# chessbot1final.net
KiCad netlist of a schematic drawn in EAGLE
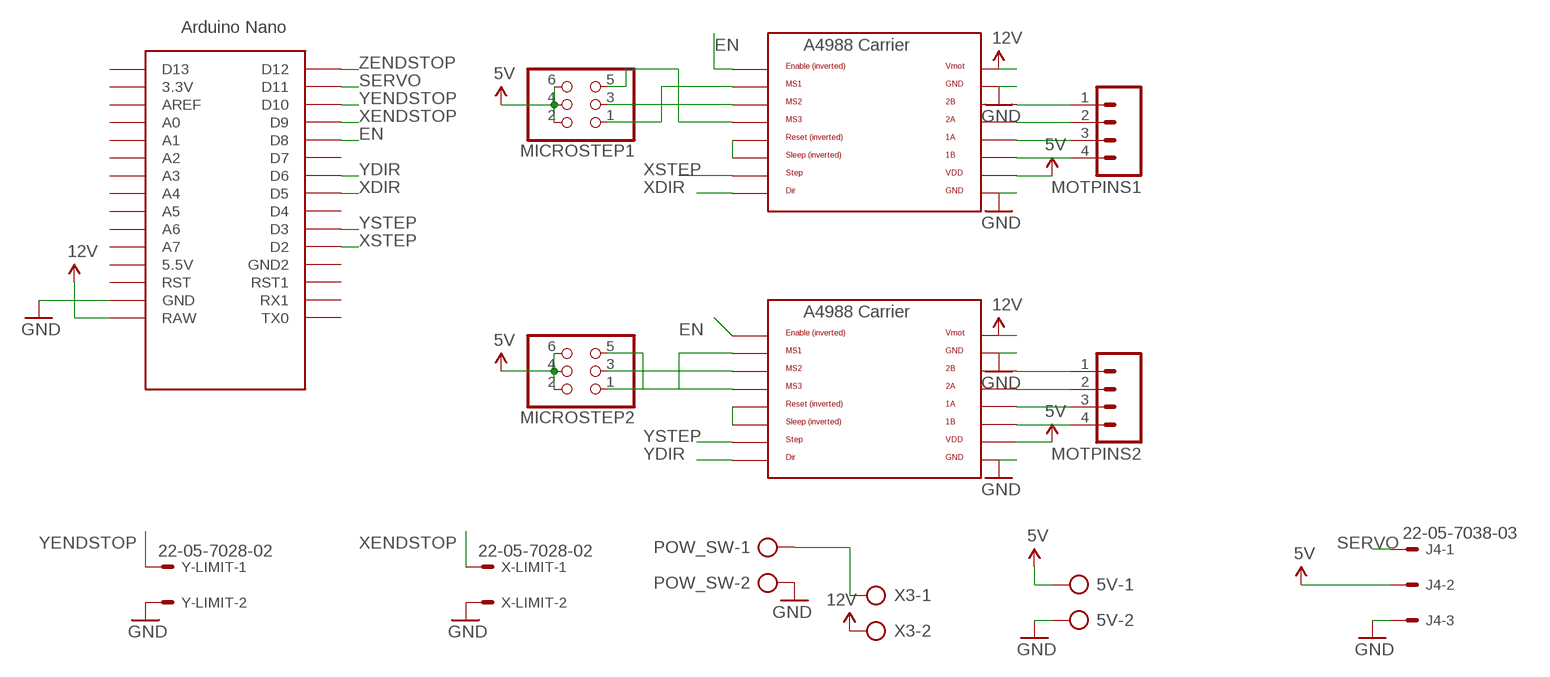
[diagram p0: schematic, sheet 1]

(export (version "E")
  (design (tool "Eeschema 10.0.6"))
  (components
    (comp (ref "5V")
      (value "AK500/2")
      (footprint "eagle-import:AK500_2")
      (libsource (lib "eagle-import") (part "AK500/2"))
    )
    (comp (ref "J4")
      (value "22-05-7038-03")
      (footprint "eagle-import:7395-03")
      (libsource (lib "eagle-import") (part "22-?-0305-7038"))
    )
    (comp (ref "MICROSTEP1")
      (value "PINHD-2X3")
      (footprint "eagle-import:2X03")
      (libsource (lib "eagle-import") (part "PINHD-2X3"))
    )
    (comp (ref "MICROSTEP2")
      (value "PINHD-2X3")
      (footprint "eagle-import:2X03")
      (libsource (lib "eagle-import") (part "PINHD-2X3"))
    )
    (comp (ref "MOTPINS1")
      (value "M04PTH")
      (footprint "eagle-import:1X04")
      (libsource (lib "eagle-import") (part "M04PTH"))
    )
    (comp (ref "MOTPINS2")
      (value "M04PTH")
      (footprint "eagle-import:1X04")
      (libsource (lib "eagle-import") (part "M04PTH"))
    )
    (comp (ref "POW_SW")
      (value "AK500/2")
      (footprint "eagle-import:AK500_2")
      (libsource (lib "eagle-import") (part "AK500/2"))
    )
    (comp (ref "U$1")
      (value "A4988BREAKOUT")
      (footprint "eagle-import:A4988BREAKOUT")
      (libsource (lib "eagle-import") (part "A4988BREAKOUT"))
    )
    (comp (ref "U$2")
      (value "A4988BREAKOUT")
      (footprint "eagle-import:A4988BREAKOUT")
      (libsource (lib "eagle-import") (part "A4988BREAKOUT"))
    )
    (comp (ref "U$3")
      (value "NANO")
      (footprint "eagle-import:NANO")
      (libsource (lib "eagle-import") (part "NANO"))
    )
    (comp (ref "X-LIMIT")
      (value "22-05-7028-02")
      (footprint "eagle-import:7395-02")
      (libsource (lib "eagle-import") (part "22-?-0205-7028"))
    )
    (comp (ref "X3")
      (value "AK500/2")
      (footprint "eagle-import:AK500_2")
      (libsource (lib "eagle-import") (part "AK500/2"))
    )
    (comp (ref "Y-LIMIT")
      (value "22-05-7028-02")
      (footprint "eagle-import:7395-02")
      (libsource (lib "eagle-import") (part "22-?-0205-7028"))
    )
  )
  (nets
    (net (code "1") (name "/EN") (class "Default")
      (node (ref "U$1") (pin "EN") (pinfunction "EN_EN") (pintype "input"))
      (node (ref "U$2") (pin "EN") (pinfunction "EN_EN") (pintype "input"))
      (node (ref "U$3") (pin "D8") (pinfunction "D8_D8") (pintype "bidirectional"))
    )
    (net (code "2") (name "/SERVO") (class "Default")
      (node (ref "J4") (pin "1") (pinfunction "S_1") (pintype "passive"))
      (node (ref "U$3") (pin "D11") (pinfunction "D11_D11") (pintype "bidirectional"))
    )
    (net (code "3") (name "/XDIR") (class "Default")
      (node (ref "U$2") (pin "DIR") (pinfunction "DIR_DIR") (pintype "input"))
      (node (ref "U$3") (pin "D5") (pinfunction "D5_D5") (pintype "bidirectional"))
    )
    (net (code "4") (name "/XENDSTOP") (class "Default")
      (node (ref "U$3") (pin "D9") (pinfunction "D9_D9") (pintype "bidirectional"))
      (node (ref "X-LIMIT") (pin "1") (pinfunction "S_1") (pintype "passive"))
    )
    (net (code "5") (name "/XSTEP") (class "Default")
      (node (ref "U$2") (pin "STEP") (pinfunction "STEP_STEP") (pintype "input"))
      (node (ref "U$3") (pin "D2") (pinfunction "D2_D2") (pintype "bidirectional"))
    )
    (net (code "6") (name "/YDIR") (class "Default")
      (node (ref "U$1") (pin "DIR") (pinfunction "DIR_DIR") (pintype "input"))
      (node (ref "U$3") (pin "D6") (pinfunction "D6_D6") (pintype "bidirectional"))
    )
    (net (code "7") (name "/YENDSTOP") (class "Default")
      (node (ref "U$3") (pin "D10") (pinfunction "D10_D10") (pintype "bidirectional"))
      (node (ref "Y-LIMIT") (pin "1") (pinfunction "S_1") (pintype "passive"))
    )
    (net (code "8") (name "/YSTEP") (class "Default")
      (node (ref "U$1") (pin "STEP") (pinfunction "STEP_STEP") (pintype "input"))
      (node (ref "U$3") (pin "D3") (pinfunction "D3_D3") (pintype "bidirectional"))
    )
    (net (code "9") (name "/ZENDSTOP") (class "Default")
      (node (ref "U$3") (pin "D12") (pinfunction "D12_D12") (pintype "bidirectional"))
    )
    (net (code "10") (name "5V") (class "Default")
      (node (ref "5V") (pin "1") (pinfunction "KL_1") (pintype "passive"))
      (node (ref "J4") (pin "2") (pinfunction "S_2") (pintype "passive"))
      (node (ref "MICROSTEP1") (pin "2") (pinfunction "2_2") (pintype "passive"))
      (node (ref "MICROSTEP1") (pin "4") (pinfunction "4_4") (pintype "passive"))
      (node (ref "MICROSTEP1") (pin "6") (pinfunction "6_6") (pintype "passive"))
      (node (ref "MICROSTEP2") (pin "2") (pinfunction "2_2") (pintype "passive"))
      (node (ref "MICROSTEP2") (pin "4") (pinfunction "4_4") (pintype "passive"))
      (node (ref "MICROSTEP2") (pin "6") (pinfunction "6_6") (pintype "passive"))
      (node (ref "U$1") (pin "VDD") (pinfunction "VDD_VDD") (pintype "power_in"))
      (node (ref "U$2") (pin "VDD") (pinfunction "VDD_VDD") (pintype "power_in"))
    )
    (net (code "11") (name "12V") (class "Default")
      (node (ref "U$1") (pin "VMOT") (pinfunction "VMOT_VMOT") (pintype "power_in"))
      (node (ref "U$2") (pin "VMOT") (pinfunction "VMOT_VMOT") (pintype "power_in"))
      (node (ref "U$3") (pin "RAW") (pinfunction "RAW_RAW") (pintype "bidirectional"))
      (node (ref "X3") (pin "2") (pinfunction "KL_2") (pintype "passive"))
    )
    (net (code "12") (name "GND") (class "Default")
      (node (ref "5V") (pin "2") (pinfunction "KL_2") (pintype "passive"))
      (node (ref "J4") (pin "3") (pinfunction "S_3") (pintype "passive"))
      (node (ref "POW_SW") (pin "2") (pinfunction "KL_2") (pintype "passive"))
      (node (ref "U$1") (pin "GND") (pinfunction "GND_GND") (pintype "power_in"))
      (node (ref "U$1") (pin "GND@0") (pinfunction "GND_GND@0") (pintype "power_in"))
      (node (ref "U$2") (pin "GND") (pinfunction "GND_GND") (pintype "power_in"))
      (node (ref "U$2") (pin "GND@0") (pinfunction "GND_GND@0") (pintype "power_in"))
      (node (ref "U$3") (pin "GND") (pinfunction "GND_GND") (pintype "bidirectional"))
      (node (ref "X-LIMIT") (pin "2") (pinfunction "S_2") (pintype "passive"))
      (node (ref "Y-LIMIT") (pin "2") (pinfunction "S_2") (pintype "passive"))
    )
    (net (code "13") (name "Net-(MICROSTEP1-Pad1)") (class "Default")
      (node (ref "MICROSTEP1") (pin "1") (pinfunction "1_1") (pintype "passive"))
      (node (ref "U$2") (pin "MS1") (pinfunction "MS1_MS1") (pintype "input"))
    )
    (net (code "14") (name "Net-(MICROSTEP1-Pad3)") (class "Default")
      (node (ref "MICROSTEP1") (pin "3") (pinfunction "3_3") (pintype "passive"))
      (node (ref "U$2") (pin "MS2") (pinfunction "MS2_MS2") (pintype "input"))
    )
    (net (code "15") (name "Net-(MICROSTEP1-Pad5)") (class "Default")
      (node (ref "MICROSTEP1") (pin "5") (pinfunction "5_5") (pintype "passive"))
      (node (ref "U$2") (pin "MS3") (pinfunction "MS3_MS3") (pintype "input"))
    )
    (net (code "16") (name "Net-(MICROSTEP2-Pad1)") (class "Default")
      (node (ref "MICROSTEP2") (pin "1") (pinfunction "1_1") (pintype "passive"))
      (node (ref "U$1") (pin "MS1") (pinfunction "MS1_MS1") (pintype "input"))
    )
    (net (code "17") (name "Net-(MICROSTEP2-Pad3)") (class "Default")
      (node (ref "MICROSTEP2") (pin "3") (pinfunction "3_3") (pintype "passive"))
      (node (ref "U$1") (pin "MS2") (pinfunction "MS2_MS2") (pintype "input"))
    )
    (net (code "18") (name "Net-(MICROSTEP2-Pad5)") (class "Default")
      (node (ref "MICROSTEP2") (pin "5") (pinfunction "5_5") (pintype "passive"))
      (node (ref "U$1") (pin "MS3") (pinfunction "MS3_MS3") (pintype "input"))
    )
    (net (code "19") (name "Net-(MOTPINS1-Pad1)") (class "Default")
      (node (ref "MOTPINS1") (pin "1") (pinfunction "1_1") (pintype "passive"))
      (node (ref "U$2") (pin "2B") (pinfunction "2B_2B") (pintype "output"))
    )
    (net (code "20") (name "Net-(MOTPINS1-Pad2)") (class "Default")
      (node (ref "MOTPINS1") (pin "2") (pinfunction "2_2") (pintype "passive"))
      (node (ref "U$2") (pin "2A") (pinfunction "2A_2A") (pintype "output"))
    )
    (net (code "21") (name "Net-(MOTPINS1-Pad3)") (class "Default")
      (node (ref "MOTPINS1") (pin "3") (pinfunction "3_3") (pintype "passive"))
      (node (ref "U$2") (pin "1A") (pinfunction "1A_1A") (pintype "output"))
    )
    (net (code "22") (name "Net-(MOTPINS1-Pad4)") (class "Default")
      (node (ref "MOTPINS1") (pin "4") (pinfunction "4_4") (pintype "passive"))
      (node (ref "U$2") (pin "1B") (pinfunction "1B_1B") (pintype "output"))
    )
    (net (code "23") (name "Net-(MOTPINS2-Pad1)") (class "Default")
      (node (ref "MOTPINS2") (pin "1") (pinfunction "1_1") (pintype "passive"))
      (node (ref "U$1") (pin "2B") (pinfunction "2B_2B") (pintype "output"))
    )
    (net (code "24") (name "Net-(MOTPINS2-Pad2)") (class "Default")
      (node (ref "MOTPINS2") (pin "2") (pinfunction "2_2") (pintype "passive"))
      (node (ref "U$1") (pin "2A") (pinfunction "2A_2A") (pintype "output"))
    )
    (net (code "25") (name "Net-(MOTPINS2-Pad3)") (class "Default")
      (node (ref "MOTPINS2") (pin "3") (pinfunction "3_3") (pintype "passive"))
      (node (ref "U$1") (pin "1A") (pinfunction "1A_1A") (pintype "output"))
    )
    (net (code "26") (name "Net-(MOTPINS2-Pad4)") (class "Default")
      (node (ref "MOTPINS2") (pin "4") (pinfunction "4_4") (pintype "passive"))
      (node (ref "U$1") (pin "1B") (pinfunction "1B_1B") (pintype "output"))
    )
    (net (code "27") (name "Net-(POW_SWA-KL)") (class "Default")
      (node (ref "POW_SW") (pin "1") (pinfunction "KL_1") (pintype "passive"))
      (node (ref "X3") (pin "1") (pinfunction "KL_1") (pintype "passive"))
    )
    (net (code "28") (name "Net-(U$1-SLEEP)") (class "Default")
      (node (ref "U$1") (pin "RST") (pinfunction "RST_RST") (pintype "input"))
      (node (ref "U$1") (pin "SLP") (pinfunction "SLEEP_SLP") (pintype "input"))
    )
    (net (code "29") (name "Net-(U$2-SLEEP)") (class "Default")
      (node (ref "U$2") (pin "RST") (pinfunction "RST_RST") (pintype "input"))
      (node (ref "U$2") (pin "SLP") (pinfunction "SLEEP_SLP") (pintype "input"))
    )
    (net (code "30") (name "unconnected-(U$3-5.5V-Pad5V)") (class "Default")
      (node (ref "U$3") (pin "5V") (pinfunction "5.5V_5V") (pintype "bidirectional"))
    )
    (net (code "31") (name "unconnected-(U$3-GND2-PadGND1)") (class "Default")
      (node (ref "U$3") (pin "GND1") (pinfunction "GND2_GND1") (pintype "bidirectional"))
    )
    (net (code "32") (name "unconnected-(U$3-Pad3.3V)") (class "Default")
      (node (ref "U$3") (pin "3.3V") (pinfunction "3.3V_3.3V") (pintype "bidirectional"))
    )
    (net (code "33") (name "unconnected-(U$3-PadA0)") (class "Default")
      (node (ref "U$3") (pin "A0") (pinfunction "A0_A0") (pintype "bidirectional"))
    )
    (net (code "34") (name "unconnected-(U$3-PadA1)") (class "Default")
      (node (ref "U$3") (pin "A1") (pinfunction "A1_A1") (pintype "bidirectional"))
    )
    (net (code "35") (name "unconnected-(U$3-PadA2)") (class "Default")
      (node (ref "U$3") (pin "A2") (pinfunction "A2_A2") (pintype "bidirectional"))
    )
    (net (code "36") (name "unconnected-(U$3-PadA3)") (class "Default")
      (node (ref "U$3") (pin "A3") (pinfunction "A3_A3") (pintype "bidirectional"))
    )
    (net (code "37") (name "unconnected-(U$3-PadA4)") (class "Default")
      (node (ref "U$3") (pin "A4") (pinfunction "A4_A4") (pintype "bidirectional"))
    )
    (net (code "38") (name "unconnected-(U$3-PadA5)") (class "Default")
      (node (ref "U$3") (pin "A5") (pinfunction "A5_A5") (pintype "bidirectional"))
    )
    (net (code "39") (name "unconnected-(U$3-PadA6)") (class "Default")
      (node (ref "U$3") (pin "A6") (pinfunction "A6_A6") (pintype "bidirectional"))
    )
    (net (code "40") (name "unconnected-(U$3-PadA7)") (class "Default")
      (node (ref "U$3") (pin "A7") (pinfunction "A7_A7") (pintype "bidirectional"))
    )
    (net (code "41") (name "unconnected-(U$3-PadAREF)") (class "Default")
      (node (ref "U$3") (pin "AREF") (pinfunction "AREF_AREF") (pintype "bidirectional"))
    )
    (net (code "42") (name "unconnected-(U$3-PadD4)") (class "Default")
      (node (ref "U$3") (pin "D4") (pinfunction "D4_D4") (pintype "bidirectional"))
    )
    (net (code "43") (name "unconnected-(U$3-PadD7)") (class "Default")
      (node (ref "U$3") (pin "D7") (pinfunction "D7_D7") (pintype "bidirectional"))
    )
    (net (code "44") (name "unconnected-(U$3-PadD13)") (class "Default")
      (node (ref "U$3") (pin "D13") (pinfunction "D13_D13") (pintype "bidirectional"))
    )
    (net (code "45") (name "unconnected-(U$3-PadICSP1)") (class "Default")
      (node (ref "U$3") (pin "ICSP1") (pinfunction "ICSP1_ICSP1") (pintype "bidirectional"))
    )
    (net (code "46") (name "unconnected-(U$3-PadICSP2)") (class "Default")
      (node (ref "U$3") (pin "ICSP2") (pinfunction "ICSP2_ICSP2") (pintype "bidirectional"))
    )
    (net (code "47") (name "unconnected-(U$3-PadICSP3)") (class "Default")
      (node (ref "U$3") (pin "ICSP3") (pinfunction "ICSP3_ICSP3") (pintype "bidirectional"))
    )
    (net (code "48") (name "unconnected-(U$3-PadICSP4)") (class "Default")
      (node (ref "U$3") (pin "ICSP4") (pinfunction "ICSP4_ICSP4") (pintype "bidirectional"))
    )
    (net (code "49") (name "unconnected-(U$3-PadICSP5)") (class "Default")
      (node (ref "U$3") (pin "ICSP5") (pinfunction "ICSP5_ICSP5") (pintype "bidirectional"))
    )
    (net (code "50") (name "unconnected-(U$3-PadICSP6)") (class "Default")
      (node (ref "U$3") (pin "ICSP6") (pinfunction "ICSP6_ICSP6") (pintype "bidirectional"))
    )
    (net (code "51") (name "unconnected-(U$3-PadRST)") (class "Default")
      (node (ref "U$3") (pin "RST") (pinfunction "RST_RST") (pintype "bidirectional"))
    )
    (net (code "52") (name "unconnected-(U$3-PadRST1)") (class "Default")
      (node (ref "U$3") (pin "RST1") (pinfunction "RST1_RST1") (pintype "bidirectional"))
    )
    (net (code "53") (name "unconnected-(U$3-PadRX1)") (class "Default")
      (node (ref "U$3") (pin "RX1") (pinfunction "RX1_RX1") (pintype "bidirectional"))
    )
    (net (code "54") (name "unconnected-(U$3-PadTX0)") (class "Default")
      (node (ref "U$3") (pin "TX0") (pinfunction "TX0_TX0") (pintype "bidirectional"))
    )
  )
)
